# Connector.net
KiCad netlist of a schematic drawn in Altium Designer
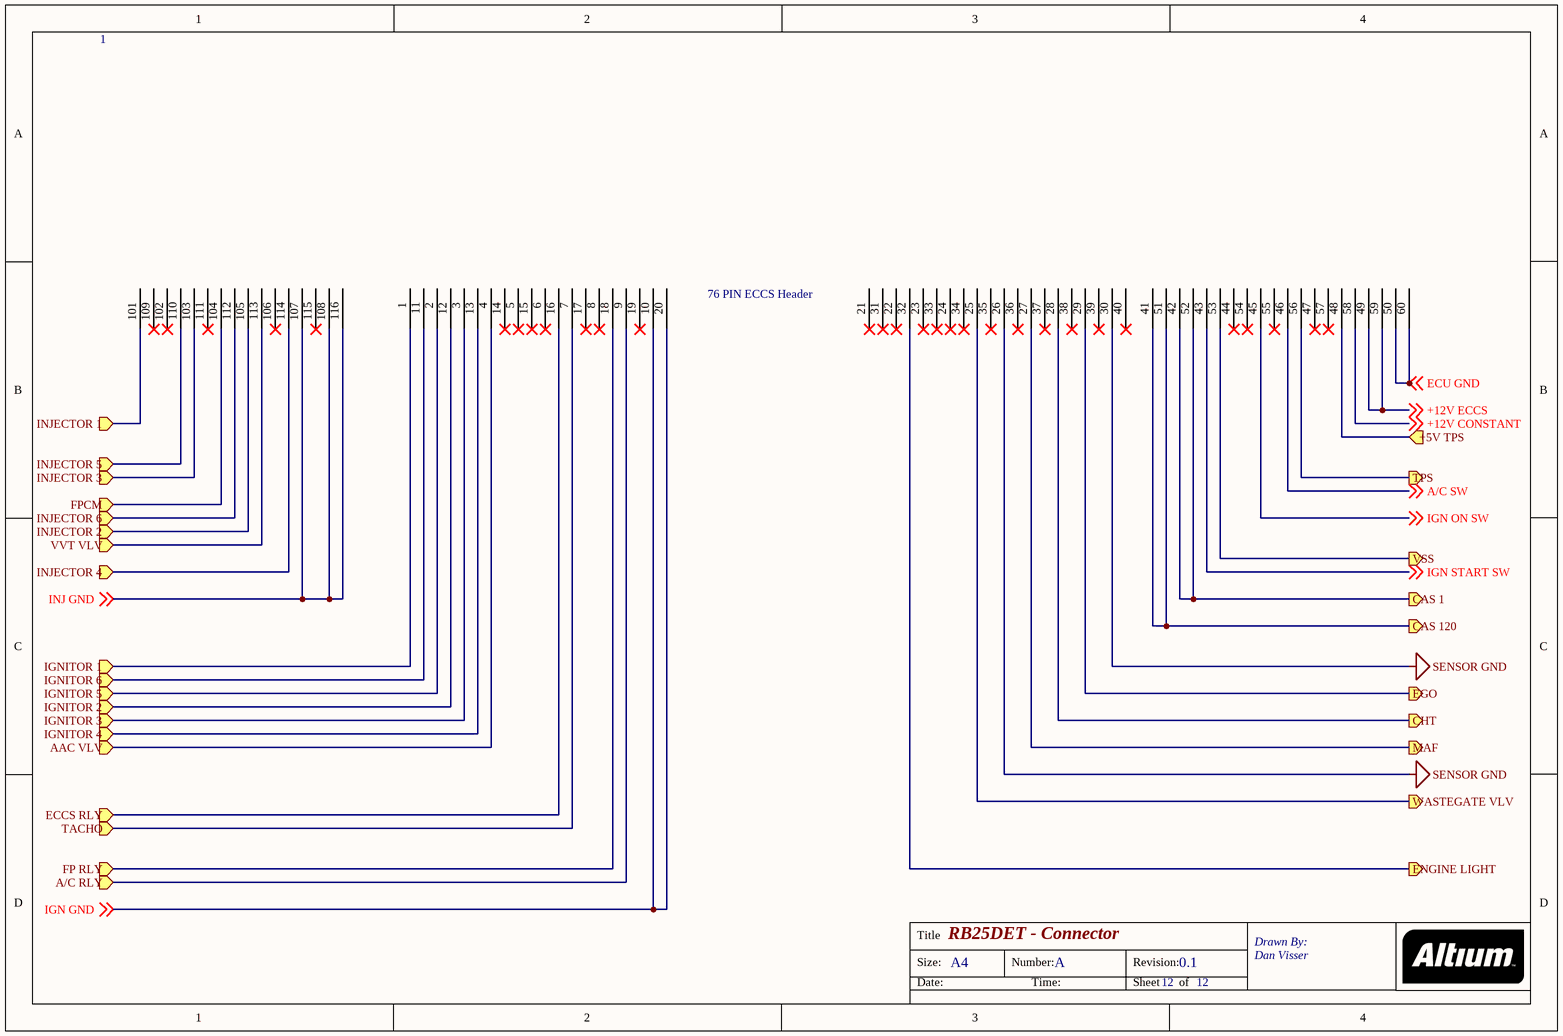
[diagram p0: Connector.SchDoc]

(export (version "E")
  (design (tool "Eeschema 10.0.6"))
  (components
    (comp (ref "1")
      (value "76 PIN ECCS Header")
      (libsource (lib "FreeEMS Schematic Library") (part "76 PIN ECCS Header"))
    )
  )
  (nets
    (net (code "1") (name "+12V CONSTANT") (class "Default") (node (ref "1") (pin "58") (pintype "passive")))
    (net (code "2") (name "+12V ECCS") (class "Default")
      (node (ref "1") (pin "49") (pintype "passive"))
      (node (ref "1") (pin "59") (pintype "passive"))
    )
    (net (code "3") (name "/+5V TPS") (class "Default") (node (ref "1") (pin "48") (pintype "passive")))
    (net (code "4") (name "/AAC VLV") (class "Default") (node (ref "1") (pin "4") (pintype "passive")))
    (net (code "5") (name "/A{slash}C RLY") (class "Default") (node (ref "1") (pin "9") (pintype "passive")))
    (net (code "6") (name "/CAS 1") (class "Default")
      (node (ref "1") (pin "42") (pintype "passive"))
      (node (ref "1") (pin "52") (pintype "passive"))
    )
    (net (code "7") (name "/CAS 120") (class "Default")
      (node (ref "1") (pin "41") (pintype "passive"))
      (node (ref "1") (pin "51") (pintype "passive"))
    )
    (net (code "8") (name "/CHT") (class "Default") (node (ref "1") (pin "28") (pintype "passive")))
    (net (code "9") (name "/ECCS RLY") (class "Default") (node (ref "1") (pin "16") (pintype "passive")))
    (net (code "10") (name "/EGO") (class "Default") (node (ref "1") (pin "29") (pintype "passive")))
    (net (code "11") (name "/ENGINE LIGHT") (class "Default") (node (ref "1") (pin "32") (pintype "passive")))
    (net (code "12") (name "/FP RLY") (class "Default") (node (ref "1") (pin "18") (pintype "passive")))
    (net (code "13") (name "/FPCM") (class "Default") (node (ref "1") (pin "104") (pintype "passive")))
    (net (code "14") (name "/IGNITOR 1") (class "Default") (node (ref "1") (pin "1") (pintype "passive")))
    (net (code "15") (name "/IGNITOR 2") (class "Default") (node (ref "1") (pin "12") (pintype "passive")))
    (net (code "16") (name "/IGNITOR 3") (class "Default") (node (ref "1") (pin "3") (pintype "passive")))
    (net (code "17") (name "/IGNITOR 4") (class "Default") (node (ref "1") (pin "13") (pintype "passive")))
    (net (code "18") (name "/IGNITOR 5") (class "Default") (node (ref "1") (pin "2") (pintype "passive")))
    (net (code "19") (name "/IGNITOR 6") (class "Default") (node (ref "1") (pin "11") (pintype "passive")))
    (net (code "20") (name "/INJECTOR 1") (class "Default") (node (ref "1") (pin "101") (pintype "passive")))
    (net (code "21") (name "/INJECTOR 2") (class "Default") (node (ref "1") (pin "105") (pintype "passive")))
    (net (code "22") (name "/INJECTOR 3") (class "Default") (node (ref "1") (pin "103") (pintype "passive")))
    (net (code "23") (name "/INJECTOR 4") (class "Default") (node (ref "1") (pin "114") (pintype "passive")))
    (net (code "24") (name "/INJECTOR 5") (class "Default") (node (ref "1") (pin "110") (pintype "passive")))
    (net (code "25") (name "/INJECTOR 6") (class "Default") (node (ref "1") (pin "112") (pintype "passive")))
    (net (code "26") (name "/MAF") (class "Default") (node (ref "1") (pin "27") (pintype "passive")))
    (net (code "27") (name "/TACHO") (class "Default") (node (ref "1") (pin "7") (pintype "passive")))
    (net (code "28") (name "/TPS") (class "Default") (node (ref "1") (pin "56") (pintype "passive")))
    (net (code "29") (name "/VSS") (class "Default") (node (ref "1") (pin "53") (pintype "passive")))
    (net (code "30") (name "/VVT VLV") (class "Default") (node (ref "1") (pin "113") (pintype "passive")))
    (net (code "31") (name "/WASTEGATE VLV") (class "Default")
      (node (ref "1") (pin "25") (pintype "passive"))
    )
    (net (code "32") (name "A{slash}C SW") (class "Default") (node (ref "1") (pin "46") (pintype "passive")))
    (net (code "33") (name "ECU GND") (class "Default")
      (node (ref "1") (pin "50") (pintype "passive"))
      (node (ref "1") (pin "60") (pintype "passive"))
    )
    (net (code "34") (name "IGN GND") (class "Default")
      (node (ref "1") (pin "10") (pintype "passive"))
      (node (ref "1") (pin "20") (pintype "passive"))
    )
    (net (code "35") (name "IGN ON SW") (class "Default") (node (ref "1") (pin "45") (pintype "passive")))
    (net (code "36") (name "IGN START SW") (class "Default") (node (ref "1") (pin "43") (pintype "passive")))
    (net (code "37") (name "INJ GND") (class "Default")
      (node (ref "1") (pin "107") (pintype "passive"))
      (node (ref "1") (pin "108") (pintype "passive"))
      (node (ref "1") (pin "116") (pintype "passive"))
    )
    (net (code "38") (name "SENSOR GND") (class "Default")
      (node (ref "1") (pin "26") (pintype "passive"))
      (node (ref "1") (pin "30") (pintype "passive"))
    )
    (net (code "39") (name "unconnected-(1-Pad5)") (class "Default")
      (node (ref "1") (pin "5") (pintype "passive+no_connect"))
    )
    (net (code "40") (name "unconnected-(1-Pad6)") (class "Default")
      (node (ref "1") (pin "6") (pintype "passive+no_connect"))
    )
    (net (code "41") (name "unconnected-(1-Pad8)") (class "Default")
      (node (ref "1") (pin "8") (pintype "passive+no_connect"))
    )
    (net (code "42") (name "unconnected-(1-Pad14)") (class "Default")
      (node (ref "1") (pin "14") (pintype "passive+no_connect"))
    )
    (net (code "43") (name "unconnected-(1-Pad15)") (class "Default")
      (node (ref "1") (pin "15") (pintype "passive+no_connect"))
    )
    (net (code "44") (name "unconnected-(1-Pad17)") (class "Default")
      (node (ref "1") (pin "17") (pintype "passive+no_connect"))
    )
    (net (code "45") (name "unconnected-(1-Pad19)") (class "Default")
      (node (ref "1") (pin "19") (pintype "passive+no_connect"))
    )
    (net (code "46") (name "unconnected-(1-Pad21)") (class "Default")
      (node (ref "1") (pin "21") (pintype "passive+no_connect"))
    )
    (net (code "47") (name "unconnected-(1-Pad22)") (class "Default")
      (node (ref "1") (pin "22") (pintype "passive+no_connect"))
    )
    (net (code "48") (name "unconnected-(1-Pad23)") (class "Default")
      (node (ref "1") (pin "23") (pintype "passive+no_connect"))
    )
    (net (code "49") (name "unconnected-(1-Pad24)") (class "Default")
      (node (ref "1") (pin "24") (pintype "passive+no_connect"))
    )
    (net (code "50") (name "unconnected-(1-Pad31)") (class "Default")
      (node (ref "1") (pin "31") (pintype "passive+no_connect"))
    )
    (net (code "51") (name "unconnected-(1-Pad33)") (class "Default")
      (node (ref "1") (pin "33") (pintype "passive+no_connect"))
    )
    (net (code "52") (name "unconnected-(1-Pad34)") (class "Default")
      (node (ref "1") (pin "34") (pintype "passive+no_connect"))
    )
    (net (code "53") (name "unconnected-(1-Pad35)") (class "Default")
      (node (ref "1") (pin "35") (pintype "passive+no_connect"))
    )
    (net (code "54") (name "unconnected-(1-Pad36)") (class "Default")
      (node (ref "1") (pin "36") (pintype "passive+no_connect"))
    )
    (net (code "55") (name "unconnected-(1-Pad37)") (class "Default")
      (node (ref "1") (pin "37") (pintype "passive+no_connect"))
    )
    (net (code "56") (name "unconnected-(1-Pad38)") (class "Default")
      (node (ref "1") (pin "38") (pintype "passive+no_connect"))
    )
    (net (code "57") (name "unconnected-(1-Pad39)") (class "Default")
      (node (ref "1") (pin "39") (pintype "passive+no_connect"))
    )
    (net (code "58") (name "unconnected-(1-Pad40)") (class "Default")
      (node (ref "1") (pin "40") (pintype "passive+no_connect"))
    )
    (net (code "59") (name "unconnected-(1-Pad44)") (class "Default")
      (node (ref "1") (pin "44") (pintype "passive+no_connect"))
    )
    (net (code "60") (name "unconnected-(1-Pad47)") (class "Default")
      (node (ref "1") (pin "47") (pintype "passive+no_connect"))
    )
    (net (code "61") (name "unconnected-(1-Pad54)") (class "Default")
      (node (ref "1") (pin "54") (pintype "passive+no_connect"))
    )
    (net (code "62") (name "unconnected-(1-Pad55)") (class "Default")
      (node (ref "1") (pin "55") (pintype "passive+no_connect"))
    )
    (net (code "63") (name "unconnected-(1-Pad57)") (class "Default")
      (node (ref "1") (pin "57") (pintype "passive+no_connect"))
    )
    (net (code "64") (name "unconnected-(1-Pad102)") (class "Default")
      (node (ref "1") (pin "102") (pintype "passive+no_connect"))
    )
    (net (code "65") (name "unconnected-(1-Pad106)") (class "Default")
      (node (ref "1") (pin "106") (pintype "passive+no_connect"))
    )
    (net (code "66") (name "unconnected-(1-Pad109)") (class "Default")
      (node (ref "1") (pin "109") (pintype "passive+no_connect"))
    )
    (net (code "67") (name "unconnected-(1-Pad111)") (class "Default")
      (node (ref "1") (pin "111") (pintype "passive+no_connect"))
    )
    (net (code "68") (name "unconnected-(1-Pad115)") (class "Default")
      (node (ref "1") (pin "115") (pintype "passive+no_connect"))
    )
  )
)
